# 13_AdditionalFunction.net
KiCad netlist of a schematic drawn in Altium Designer
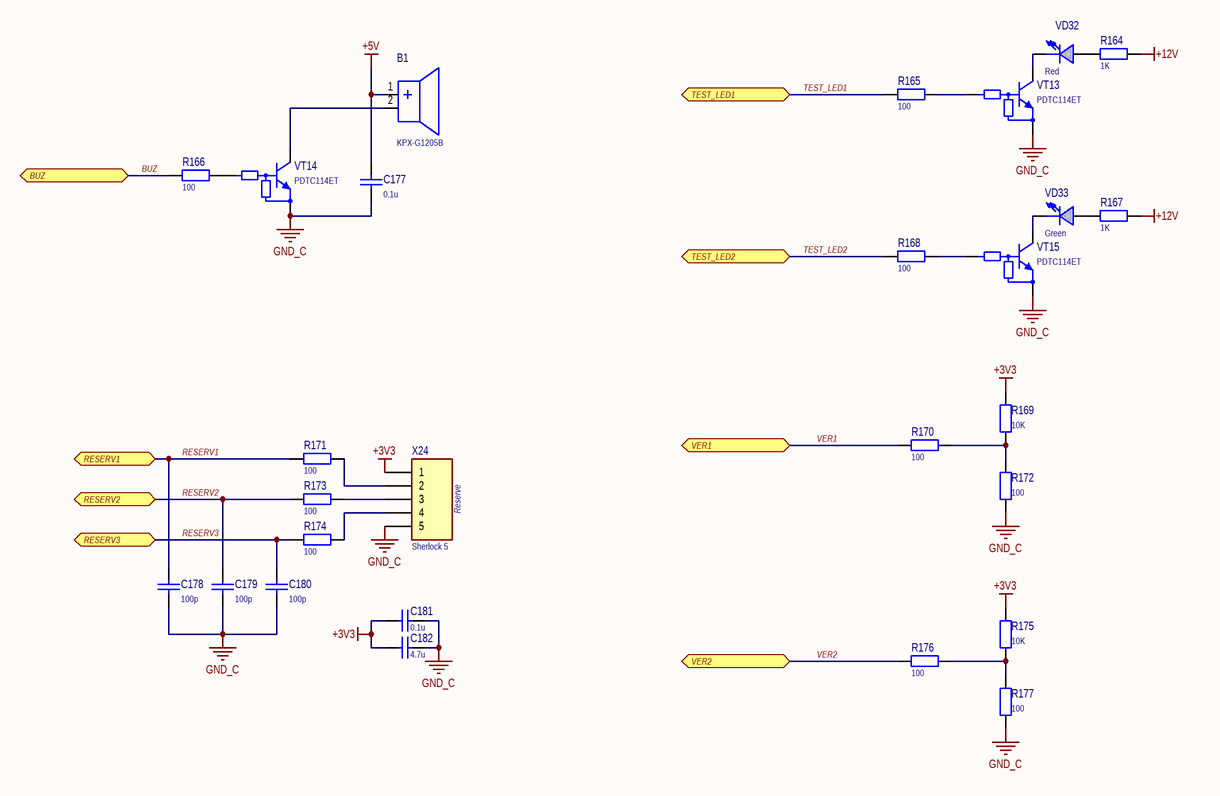
[diagram p0: 13_AdditionalFunction.SchDoc]

(export (version "E")
  (design (tool "Eeschema 10.0.6"))
  (components
    (comp (ref "B1")
      (value "KPX-G1205B")
      (footprint "mainLib:KPX-G12")
      (description "Magnetic Buzzer")
      (fields (field (name "MANUFACTURER") "KEPO"))
      (libsource (lib "mainLib") (part "KPX-G1205B"))
    )
    (comp (ref "C177")
      (value "0.1u")
      (footprint "mainLib:SMD_C_0603")
      (description "SMD C 0603 MURATA 50V 10% X7R")
      (fields (field (name "PARTNUMBER") "GRM188R71H104K") (field (name "MANUFACTURER") "MURATA"))
      (libsource (lib "mainRCLib") (part "C0603 0.1u 50V 10%"))
    )
    (comp (ref "C178")
      (value "100p")
      (footprint "mainLib:SMD_C_0603")
      (description "SMD C 0603 MURATA 100V 5% NP0")
      (fields (field (name "PARTNUMBER") "GRM1885C2A101JA01") (field (name "MANUFACTURER") "MURATA"))
      (libsource (lib "mainRCLib") (part "C0603 100p 100V 5%"))
    )
    (comp (ref "C179")
      (value "100p")
      (footprint "mainLib:SMD_C_0603")
      (description "SMD C 0603 MURATA 100V 5% NP0")
      (fields (field (name "PARTNUMBER") "GRM1885C2A101JA01") (field (name "MANUFACTURER") "MURATA"))
      (libsource (lib "mainRCLib") (part "C0603 100p 100V 5%"))
    )
    (comp (ref "C180")
      (value "100p")
      (footprint "mainLib:SMD_C_0603")
      (description "SMD C 0603 MURATA 100V 5% NP0")
      (fields (field (name "PARTNUMBER") "GRM1885C2A101JA01") (field (name "MANUFACTURER") "MURATA"))
      (libsource (lib "mainRCLib") (part "C0603 100p 100V 5%"))
    )
    (comp (ref "C181")
      (value "0.1u")
      (footprint "mainLib:SMD_C_0603")
      (description "SMD C 0603 MURATA 50V 10% X7R")
      (fields (field (name "PARTNUMBER") "GRM188R71H104K") (field (name "MANUFACTURER") "MURATA"))
      (libsource (lib "mainRCLib") (part "C0603 0.1u 50V 10%"))
    )
    (comp (ref "C182")
      (value "4.7u")
      (footprint "mainLib:SMD_C_0805")
      (description "SMD C 0805 MURATA 50V 5% NP0")
      (fields (field (name "PARTNUMBER") "GRM21BR61E475M") (field (name "MANUFACTURER") "MURATA"))
      (libsource (lib "mainRCLib") (part "C0805 4.7u 25V 20%  X5R"))
    )
    (comp (ref "R164")
      (value "1K")
      (footprint "mainLib:SMD_R_1206")
      (description "SMD R 1206 VISHAY 0.25W 200V 1% 100ppm")
      (fields (field (name "PARTNUMBER") "CRCW12061K00FK") (field (name "MANUFACTURER") "VISHAY"))
      (libsource (lib "mainRCLib") (part "R1206 1K 1%"))
    )
    (comp (ref "R165")
      (value "100")
      (footprint "SMD_R_0603")
      (description "SMD R 0603 VISHAY 0.1W 75V 1% 100ppm")
      (fields (field (name "PARTNUMBER") "CRCW0603100RFK") (field (name "MANUFACTURER") "VISHAY"))
      (libsource (lib "mainRCLib") (part "R0603 100 1%"))
    )
    (comp (ref "R166")
      (value "100")
      (footprint "SMD_R_0603")
      (description "SMD R 0603 VISHAY 0.1W 75V 1% 100ppm")
      (fields (field (name "PARTNUMBER") "CRCW0603100RFK") (field (name "MANUFACTURER") "VISHAY"))
      (libsource (lib "mainRCLib") (part "R0603 100 1%"))
    )
    (comp (ref "R167")
      (value "1K")
      (footprint "mainLib:SMD_R_1206")
      (description "SMD R 1206 VISHAY 0.25W 200V 1% 100ppm")
      (fields (field (name "PARTNUMBER") "CRCW12061K00FK") (field (name "MANUFACTURER") "VISHAY"))
      (libsource (lib "mainRCLib") (part "R1206 1K 1%"))
    )
    (comp (ref "R168")
      (value "100")
      (footprint "SMD_R_0603")
      (description "SMD R 0603 VISHAY 0.1W 75V 1% 100ppm")
      (fields (field (name "PARTNUMBER") "CRCW0603100RFK") (field (name "MANUFACTURER") "VISHAY"))
      (libsource (lib "mainRCLib") (part "R0603 100 1%"))
    )
    (comp (ref "R169")
      (value "10K")
      (footprint "SMD_R_0603")
      (description "SMD R 0603 VISHAY 0.1W 75V 1% 100ppm")
      (fields (field (name "PARTNUMBER") "CRCW060310K0FK") (field (name "MANUFACTURER") "VISHAY"))
      (libsource (lib "mainRCLib") (part "R0603 10К 1%"))
    )
    (comp (ref "R170")
      (value "100")
      (footprint "SMD_R_0603")
      (description "SMD R 0603 VISHAY 0.1W 75V 1% 100ppm")
      (fields (field (name "PARTNUMBER") "CRCW0603100RFK") (field (name "MANUFACTURER") "VISHAY"))
      (libsource (lib "mainRCLib") (part "R0603 100 1%"))
    )
    (comp (ref "R171")
      (value "100")
      (footprint "SMD_R_0603")
      (description "SMD R 0603 VISHAY 0.1W 75V 1% 100ppm")
      (fields (field (name "PARTNUMBER") "CRCW0603100RFK") (field (name "MANUFACTURER") "VISHAY"))
      (libsource (lib "mainRCLib") (part "R0603 100 1%"))
    )
    (comp (ref "R172")
      (value "100")
      (footprint "SMD_R_0603")
      (description "SMD R 0603 VISHAY 0.1W 75V 1% 100ppm")
      (fields (field (name "PARTNUMBER") "CRCW0603100RFK") (field (name "MANUFACTURER") "VISHAY"))
      (libsource (lib "") (part "R0603 100 1%_1"))
    )
    (comp (ref "R173")
      (value "100")
      (footprint "SMD_R_0603")
      (description "SMD R 0603 VISHAY 0.1W 75V 1% 100ppm")
      (fields (field (name "PARTNUMBER") "CRCW0603100RFK") (field (name "MANUFACTURER") "VISHAY"))
      (libsource (lib "mainRCLib") (part "R0603 100 1%"))
    )
    (comp (ref "R174")
      (value "100")
      (footprint "SMD_R_0603")
      (description "SMD R 0603 VISHAY 0.1W 75V 1% 100ppm")
      (fields (field (name "PARTNUMBER") "CRCW0603100RFK") (field (name "MANUFACTURER") "VISHAY"))
      (libsource (lib "mainRCLib") (part "R0603 100 1%"))
    )
    (comp (ref "R175")
      (value "10K")
      (footprint "SMD_R_0603")
      (description "SMD R 0603 VISHAY 0.1W 75V 1% 100ppm")
      (fields (field (name "PARTNUMBER") "CRCW060310K0FK") (field (name "MANUFACTURER") "VISHAY"))
      (libsource (lib "mainRCLib") (part "R0603 10К 1%"))
    )
    (comp (ref "R176")
      (value "100")
      (footprint "SMD_R_0603")
      (description "SMD R 0603 VISHAY 0.1W 75V 1% 100ppm")
      (fields (field (name "PARTNUMBER") "CRCW0603100RFK") (field (name "MANUFACTURER") "VISHAY"))
      (libsource (lib "mainRCLib") (part "R0603 100 1%"))
    )
    (comp (ref "R177")
      (value "100")
      (footprint "SMD_R_0603")
      (description "SMD R 0603 VISHAY 0.1W 75V 1% 100ppm")
      (fields (field (name "PARTNUMBER") "CRCW0603100RFK") (field (name "MANUFACTURER") "VISHAY"))
      (libsource (lib "") (part "R0603 100 1%_1"))
    )
    (comp (ref "VD32")
      (value "Red")
      (footprint "mainLib:SMD_LED_LL_Red")
      (description "LED Red SMD")
      (fields (field (name "PARTNUMBER") "LL-S172SC-2S") (field (name "MANUFACTURER") "Lucky Light"))
      (libsource (lib "mainLib") (part "LL-S172SC-2S"))
    )
    (comp (ref "VD33")
      (value "Green")
      (footprint "mainLib:SMD_LED_LL_Green")
      (description "LED Green SMD")
      (fields (field (name "PARTNUMBER") "LL-S172GC-2A") (field (name "MANUFACTURER") "Lucky Light"))
      (libsource (lib "mainLib") (part "LL-S172GC-2A"))
    )
    (comp (ref "VT13")
      (value "PDTC114ET")
      (footprint "mainLib:SOT23-3")
      (description "Digital Transistor (BRT), R1=10 kOhm, R2=10 kOhm, NPN Transistor")
      (fields (field (name "MANUFACTURER") "On Semiconductor"))
      (libsource (lib "mainLib") (part "PDTC114ET"))
    )
    (comp (ref "VT14")
      (value "PDTC114ET")
      (footprint "mainLib:SOT23-3")
      (description "Digital Transistor (BRT), R1=10 kOhm, R2=10 kOhm, NPN Transistor")
      (fields (field (name "MANUFACTURER") "On Semiconductor"))
      (libsource (lib "mainLib") (part "PDTC114ET"))
    )
    (comp (ref "VT15")
      (value "PDTC114ET")
      (footprint "mainLib:SOT23-3")
      (description "Digital Transistor (BRT), R1=10 kOhm, R2=10 kOhm, NPN Transistor")
      (fields (field (name "MANUFACTURER") "On Semiconductor"))
      (libsource (lib "mainLib") (part "PDTC114ET"))
    )
    (comp (ref "X24")
      (value "Sherlock 5")
      (footprint "mainLib:35362-0550")
      (description "Sherlock 5 Top, 2A 125V 2mm")
      (fields (field (name "PARTNUMBER") "35362-0550") (field (name "MANUFACTURER") "MOLEX"))
      (libsource (lib "mainLib") (part "35362-0550"))
    )
  )
  (nets
    (net (code "1") (name "+3V3") (class "Default")
      (node (ref "C181") (pin "1") (pinfunction "1_1") (pintype "passive"))
      (node (ref "C182") (pin "1") (pinfunction "1_1") (pintype "passive"))
      (node (ref "R169") (pin "2") (pinfunction "2_2") (pintype "passive"))
      (node (ref "R175") (pin "2") (pinfunction "2_2") (pintype "passive"))
      (node (ref "X24") (pin "1") (pinfunction "1_1") (pintype "passive"))
    )
    (net (code "2") (name "+5V") (class "Default")
      (node (ref "B1") (pin "1") (pinfunction "+_1") (pintype "passive"))
      (node (ref "C177") (pin "2") (pinfunction "2_2") (pintype "passive"))
    )
    (net (code "3") (name "+12V") (class "Default")
      (node (ref "R164") (pin "2") (pinfunction "2_2") (pintype "passive"))
      (node (ref "R167") (pin "2") (pinfunction "2_2") (pintype "passive"))
    )
    (net (code "4") (name "/BUZ") (class "Default")
      (node (ref "R166") (pin "1") (pinfunction "1_1") (pintype "passive"))
    )
    (net (code "5") (name "/RESERV1") (class "Default")
      (node (ref "C178") (pin "2") (pinfunction "2_2") (pintype "passive"))
      (node (ref "R171") (pin "1") (pinfunction "1_1") (pintype "passive"))
    )
    (net (code "6") (name "/RESERV2") (class "Default")
      (node (ref "C179") (pin "2") (pinfunction "2_2") (pintype "passive"))
      (node (ref "R173") (pin "1") (pinfunction "1_1") (pintype "passive"))
    )
    (net (code "7") (name "/RESERV3") (class "Default")
      (node (ref "C180") (pin "2") (pinfunction "2_2") (pintype "passive"))
      (node (ref "R174") (pin "1") (pinfunction "1_1") (pintype "passive"))
    )
    (net (code "8") (name "/TEST_LED1") (class "Default")
      (node (ref "R165") (pin "1") (pinfunction "1_1") (pintype "passive"))
    )
    (net (code "9") (name "/TEST_LED2") (class "Default")
      (node (ref "R168") (pin "1") (pinfunction "1_1") (pintype "passive"))
    )
    (net (code "10") (name "/VER1") (class "Default")
      (node (ref "R170") (pin "1") (pinfunction "1_1") (pintype "passive"))
    )
    (net (code "11") (name "/VER2") (class "Default")
      (node (ref "R176") (pin "1") (pinfunction "1_1") (pintype "passive"))
    )
    (net (code "12") (name "GND_C") (class "Default")
      (node (ref "C177") (pin "1") (pinfunction "1_1") (pintype "passive"))
      (node (ref "C178") (pin "1") (pinfunction "1_1") (pintype "passive"))
      (node (ref "C179") (pin "1") (pinfunction "1_1") (pintype "passive"))
      (node (ref "C180") (pin "1") (pinfunction "1_1") (pintype "passive"))
      (node (ref "C181") (pin "2") (pinfunction "2_2") (pintype "passive"))
      (node (ref "C182") (pin "2") (pinfunction "2_2") (pintype "passive"))
      (node (ref "R172") (pin "1") (pinfunction "1_1") (pintype "passive"))
      (node (ref "R177") (pin "1") (pinfunction "1_1") (pintype "passive"))
      (node (ref "VT13") (pin "2") (pinfunction "E_2") (pintype "passive"))
      (node (ref "VT14") (pin "2") (pinfunction "E_2") (pintype "passive"))
      (node (ref "VT15") (pin "2") (pinfunction "E_2") (pintype "passive"))
      (node (ref "X24") (pin "5") (pinfunction "5_5") (pintype "passive"))
    )
    (net (code "13") (name "Net-(B1--)") (class "Default")
      (node (ref "B1") (pin "2") (pinfunction "-_2") (pintype "passive"))
      (node (ref "VT14") (pin "3") (pinfunction "C_3") (pintype "passive"))
    )
    (net (code "14") (name "Net-(R169-Pad1)") (class "Default")
      (node (ref "R169") (pin "1") (pinfunction "1_1") (pintype "passive"))
      (node (ref "R170") (pin "2") (pinfunction "2_2") (pintype "passive"))
      (node (ref "R172") (pin "2") (pinfunction "2_2") (pintype "passive"))
    )
    (net (code "15") (name "Net-(R171-Pad2)") (class "Default")
      (node (ref "R171") (pin "2") (pinfunction "2_2") (pintype "passive"))
      (node (ref "X24") (pin "2") (pinfunction "2_2") (pintype "passive"))
    )
    (net (code "16") (name "Net-(R173-Pad2)") (class "Default")
      (node (ref "R173") (pin "2") (pinfunction "2_2") (pintype "passive"))
      (node (ref "X24") (pin "3") (pinfunction "3_3") (pintype "passive"))
    )
    (net (code "17") (name "Net-(R174-Pad2)") (class "Default")
      (node (ref "R174") (pin "2") (pinfunction "2_2") (pintype "passive"))
      (node (ref "X24") (pin "4") (pinfunction "4_4") (pintype "passive"))
    )
    (net (code "18") (name "Net-(R175-Pad1)") (class "Default")
      (node (ref "R175") (pin "1") (pinfunction "1_1") (pintype "passive"))
      (node (ref "R176") (pin "2") (pinfunction "2_2") (pintype "passive"))
      (node (ref "R177") (pin "2") (pinfunction "2_2") (pintype "passive"))
    )
    (net (code "19") (name "Net-(VD32-ANODE)") (class "Default")
      (node (ref "R164") (pin "1") (pinfunction "1_1") (pintype "passive"))
      (node (ref "VD32") (pin "1") (pinfunction "ANODE_1") (pintype "passive"))
    )
    (net (code "20") (name "Net-(VD32-CATHODE)") (class "Default")
      (node (ref "VD32") (pin "2") (pinfunction "CATHODE_2") (pintype "passive"))
      (node (ref "VT13") (pin "3") (pinfunction "C_3") (pintype "passive"))
    )
    (net (code "21") (name "Net-(VD33-ANODE)") (class "Default")
      (node (ref "R167") (pin "1") (pinfunction "1_1") (pintype "passive"))
      (node (ref "VD33") (pin "1") (pinfunction "ANODE_1") (pintype "passive"))
    )
    (net (code "22") (name "Net-(VD33-CATHODE)") (class "Default")
      (node (ref "VD33") (pin "2") (pinfunction "CATHODE_2") (pintype "passive"))
      (node (ref "VT15") (pin "3") (pinfunction "C_3") (pintype "passive"))
    )
    (net (code "23") (name "Net-(VT13-B)") (class "Default")
      (node (ref "R165") (pin "2") (pinfunction "2_2") (pintype "passive"))
      (node (ref "VT13") (pin "1") (pinfunction "B_1") (pintype "passive"))
    )
    (net (code "24") (name "Net-(VT14-B)") (class "Default")
      (node (ref "R166") (pin "2") (pinfunction "2_2") (pintype "passive"))
      (node (ref "VT14") (pin "1") (pinfunction "B_1") (pintype "passive"))
    )
    (net (code "25") (name "Net-(VT15-B)") (class "Default")
      (node (ref "R168") (pin "2") (pinfunction "2_2") (pintype "passive"))
      (node (ref "VT15") (pin "1") (pinfunction "B_1") (pintype "passive"))
    )
  )
)
